# nico.net
KiCad netlist of a schematic drawn in EAGLE
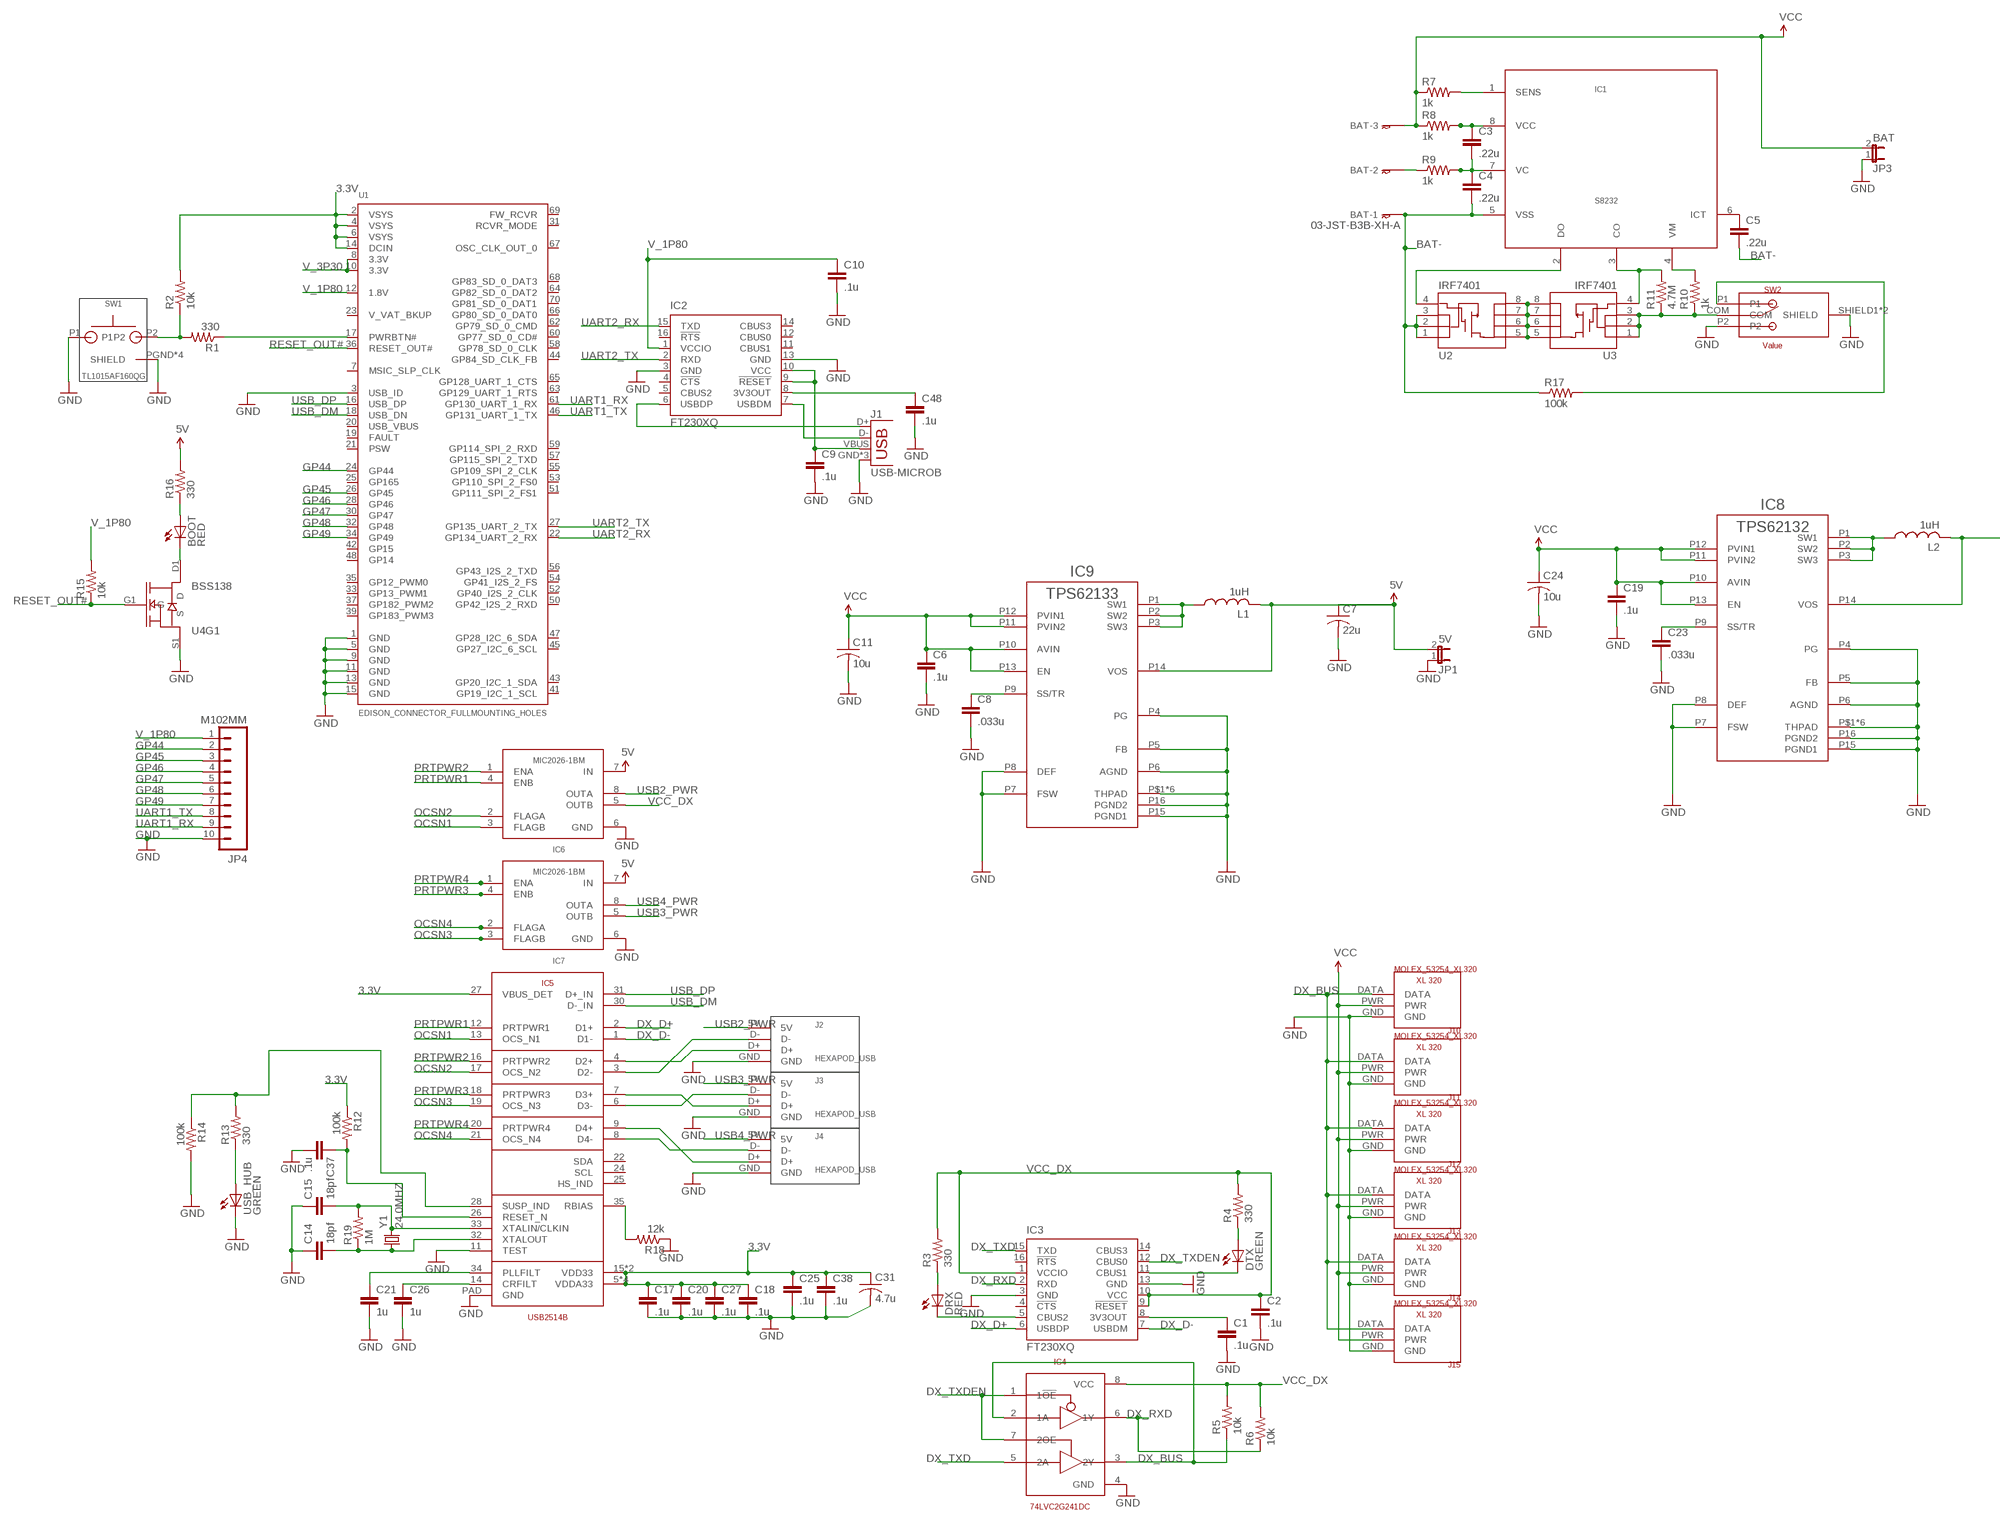
[diagram p0: schematic, sheet 1, part 1 of 2]
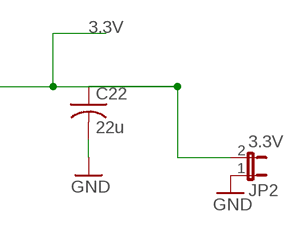
[diagram p1: schematic, sheet 1, part 2 of 2]

(export (version "E")
  (design (tool "Eeschema 10.0.6"))
  (components
    (comp (ref "BAT")
      (value "03-JST-B3B-XH-A")
      (footprint "eagle-import:B3B-XH")
      (libsource (lib "eagle-import") (part "03-JST-B3B-XH-A"))
    )
    (comp (ref "BOOT")
      (value "RED")
      (footprint "eagle-import:LED-0603")
      (libsource (lib "eagle-import") (part "LED0603"))
    )
    (comp (ref "C1")
      (value ".1u")
      (footprint "eagle-import:C0402")
      (libsource (lib "eagle-import") (part "C-EUC0402"))
    )
    (comp (ref "C2")
      (value ".1u")
      (footprint "eagle-import:C0402")
      (libsource (lib "eagle-import") (part "C-EUC0402"))
    )
    (comp (ref "C3")
      (value ".22u")
      (footprint "eagle-import:C0402")
      (libsource (lib "eagle-import") (part "C-EUC0402"))
    )
    (comp (ref "C4")
      (value ".22u")
      (footprint "eagle-import:C0402")
      (libsource (lib "eagle-import") (part "C-EUC0402"))
    )
    (comp (ref "C5")
      (value ".22u")
      (footprint "eagle-import:C0402")
      (libsource (lib "eagle-import") (part "C-EUC0402"))
    )
    (comp (ref "C6")
      (value ".1u")
      (footprint "eagle-import:C0402")
      (libsource (lib "eagle-import") (part "C-EUC0402"))
    )
    (comp (ref "C7")
      (value "22u")
      (footprint "eagle-import:C0603")
      (libsource (lib "eagle-import") (part "resistor_C-USC0603"))
    )
    (comp (ref "C8")
      (value ".033u")
      (footprint "eagle-import:C0402")
      (libsource (lib "eagle-import") (part "C-EUC0402"))
    )
    (comp (ref "C9")
      (value ".1u")
      (footprint "eagle-import:C0402")
      (libsource (lib "eagle-import") (part "C-EUC0402"))
    )
    (comp (ref "C10")
      (value ".1u")
      (footprint "eagle-import:C0402")
      (libsource (lib "eagle-import") (part "C-EUC0402"))
    )
    (comp (ref "C11")
      (value "10u")
      (footprint "eagle-import:C0805")
      (libsource (lib "eagle-import") (part "C-USC0805"))
    )
    (comp (ref "C14")
      (value "18pf")
      (footprint "eagle-import:C0402")
      (libsource (lib "eagle-import") (part "C-EUC0402"))
    )
    (comp (ref "C15")
      (value "18pf")
      (footprint "eagle-import:C0402")
      (libsource (lib "eagle-import") (part "C-EUC0402"))
    )
    (comp (ref "C17")
      (value ".1u")
      (footprint "eagle-import:C0402")
      (libsource (lib "eagle-import") (part "C-EUC0402"))
    )
    (comp (ref "C18")
      (value ".1u")
      (footprint "eagle-import:C0402")
      (libsource (lib "eagle-import") (part "C-EUC0402"))
    )
    (comp (ref "C19")
      (value ".1u")
      (footprint "eagle-import:C0402")
      (libsource (lib "eagle-import") (part "C-EUC0402"))
    )
    (comp (ref "C20")
      (value ".1u")
      (footprint "eagle-import:C0402")
      (libsource (lib "eagle-import") (part "C-EUC0402"))
    )
    (comp (ref "C21")
      (value "1u")
      (footprint "eagle-import:C0402")
      (libsource (lib "eagle-import") (part "C-EUC0402"))
    )
    (comp (ref "C22")
      (value "22u")
      (footprint "eagle-import:C0603")
      (libsource (lib "eagle-import") (part "resistor_C-USC0603"))
    )
    (comp (ref "C23")
      (value ".033u")
      (footprint "eagle-import:C0402")
      (libsource (lib "eagle-import") (part "C-EUC0402"))
    )
    (comp (ref "C24")
      (value "10u")
      (footprint "eagle-import:C0805")
      (libsource (lib "eagle-import") (part "C-USC0805"))
    )
    (comp (ref "C25")
      (value ".1u")
      (footprint "eagle-import:C0402")
      (libsource (lib "eagle-import") (part "C-EUC0402"))
    )
    (comp (ref "C26")
      (value "1u")
      (footprint "eagle-import:C0402")
      (libsource (lib "eagle-import") (part "C-EUC0402"))
    )
    (comp (ref "C27")
      (value ".1u")
      (footprint "eagle-import:C0402")
      (libsource (lib "eagle-import") (part "C-EUC0402"))
    )
    (comp (ref "C31")
      (value "4.7u")
      (footprint "eagle-import:C0603")
      (libsource (lib "eagle-import") (part "resistor_C-USC0603"))
    )
    (comp (ref "C37")
      (value ".1u")
      (footprint "eagle-import:C0402")
      (libsource (lib "eagle-import") (part "C-EUC0402"))
    )
    (comp (ref "C38")
      (value ".1u")
      (footprint "eagle-import:C0402")
      (libsource (lib "eagle-import") (part "C-EUC0402"))
    )
    (comp (ref "C48")
      (value ".1u")
      (footprint "eagle-import:C0402")
      (libsource (lib "eagle-import") (part "C-EUC0402"))
    )
    (comp (ref "DRX")
      (value "RED")
      (footprint "eagle-import:LED-0603")
      (libsource (lib "eagle-import") (part "LED0603"))
    )
    (comp (ref "DTX")
      (value "GREEN")
      (footprint "eagle-import:LED-0603")
      (libsource (lib "eagle-import") (part "LED0603"))
    )
    (comp (ref "IC1")
      (value "S8232")
      (footprint "eagle-import:TSSOP8")
      (libsource (lib "eagle-import") (part "S8232"))
    )
    (comp (ref "IC2")
      (value "FT230XQ")
      (footprint "eagle-import:QFN16")
      (libsource (lib "eagle-import") (part "FT230XQ"))
    )
    (comp (ref "IC3")
      (value "FT230XQ")
      (footprint "eagle-import:QFN16")
      (libsource (lib "eagle-import") (part "FT230XQ"))
    )
    (comp (ref "IC4")
      (value "74LVC2G241DC")
      (footprint "eagle-import:VSSOP")
      (libsource (lib "eagle-import") (part "74LVC2G241DC"))
    )
    (comp (ref "IC5")
      (value "USB2514B")
      (footprint "eagle-import:36-QFN")
      (libsource (lib "eagle-import") (part "USB2514B"))
    )
    (comp (ref "IC6")
      (value "MIC2026-1BM")
      (footprint "eagle-import:8-SOIC")
      (libsource (lib "eagle-import") (part "MIC2026-1BM"))
    )
    (comp (ref "IC7")
      (value "MIC2026-1BM")
      (footprint "eagle-import:8-SOIC")
      (libsource (lib "eagle-import") (part "MIC2026-1BM"))
    )
    (comp (ref "IC8")
      (value "TPS62132")
      (footprint "eagle-import:VQFN-16")
      (libsource (lib "eagle-import") (part "TPS62133"))
    )
    (comp (ref "IC9")
      (value "TPS62133")
      (footprint "eagle-import:VQFN-16")
      (libsource (lib "eagle-import") (part "TPS62133"))
    )
    (comp (ref "J1")
      (value "USB-MICROB")
      (footprint "eagle-import:USB-MICROB")
      (libsource (lib "eagle-import") (part "USB-MICROB"))
    )
    (comp (ref "J2")
      (value "HEXAPOD_USB")
      (footprint "eagle-import:MOLEX_53254_4POS")
      (libsource (lib "eagle-import") (part "HEXAPOD_USB"))
    )
    (comp (ref "J3")
      (value "HEXAPOD_USB")
      (footprint "eagle-import:MOLEX_53254_4POS")
      (libsource (lib "eagle-import") (part "HEXAPOD_USB"))
    )
    (comp (ref "J4")
      (value "HEXAPOD_USB")
      (footprint "eagle-import:MOLEX_53254_4POS")
      (libsource (lib "eagle-import") (part "HEXAPOD_USB"))
    )
    (comp (ref "J10")
      (value "MOLEX_53254_XL320")
      (footprint "eagle-import:MOLES_53254_XL320")
      (libsource (lib "eagle-import") (part "MOLEX_53254_XL320"))
    )
    (comp (ref "J11")
      (value "MOLEX_53254_XL320")
      (footprint "eagle-import:MOLES_53254_XL320")
      (libsource (lib "eagle-import") (part "MOLEX_53254_XL320"))
    )
    (comp (ref "J12")
      (value "MOLEX_53254_XL320")
      (footprint "eagle-import:MOLES_53254_XL320")
      (libsource (lib "eagle-import") (part "MOLEX_53254_XL320"))
    )
    (comp (ref "J13")
      (value "MOLEX_53254_XL320")
      (footprint "eagle-import:MOLES_53254_XL320")
      (libsource (lib "eagle-import") (part "MOLEX_53254_XL320"))
    )
    (comp (ref "J14")
      (value "MOLEX_53254_XL320")
      (footprint "eagle-import:MOLES_53254_XL320")
      (libsource (lib "eagle-import") (part "MOLEX_53254_XL320"))
    )
    (comp (ref "J15")
      (value "MOLEX_53254_XL320")
      (footprint "eagle-import:MOLES_53254_XL320")
      (libsource (lib "eagle-import") (part "MOLEX_53254_XL320"))
    )
    (comp (ref "JP1")
      (value "5V")
      (footprint "eagle-import:1X02")
      (libsource (lib "eagle-import") (part "JUMPER-2PTH"))
    )
    (comp (ref "JP2")
      (value "3.3V")
      (footprint "eagle-import:1X02")
      (libsource (lib "eagle-import") (part "JUMPER-2PTH"))
    )
    (comp (ref "JP3")
      (value "BAT")
      (footprint "eagle-import:1X02")
      (libsource (lib "eagle-import") (part "JUMPER-2PTH"))
    )
    (comp (ref "JP4")
      (value "M102MM")
      (footprint "eagle-import:1X10-2MM")
      (libsource (lib "eagle-import") (part "M102MM"))
    )
    (comp (ref "L1")
      (value "1uH")
      (footprint "eagle-import:L2825P")
      (libsource (lib "eagle-import") (part "L-USL2825P"))
    )
    (comp (ref "L2")
      (value "1uH")
      (footprint "eagle-import:L2825P")
      (libsource (lib "eagle-import") (part "L-USL2825P"))
    )
    (comp (ref "R1")
      (value "330")
      (footprint "eagle-import:R0402")
      (libsource (lib "eagle-import") (part "R-US_R0402"))
    )
    (comp (ref "R2")
      (value "10k")
      (footprint "eagle-import:R0402")
      (libsource (lib "eagle-import") (part "R-US_R0402"))
    )
    (comp (ref "R3")
      (value "330")
      (footprint "eagle-import:R0402")
      (libsource (lib "eagle-import") (part "R-US_R0402"))
    )
    (comp (ref "R4")
      (value "330")
      (footprint "eagle-import:R0402")
      (libsource (lib "eagle-import") (part "R-US_R0402"))
    )
    (comp (ref "R5")
      (value "10k")
      (footprint "eagle-import:R0402")
      (libsource (lib "eagle-import") (part "R-US_R0402"))
    )
    (comp (ref "R6")
      (value "10k")
      (footprint "eagle-import:R0402")
      (libsource (lib "eagle-import") (part "R-US_R0402"))
    )
    (comp (ref "R7")
      (value "1k")
      (footprint "eagle-import:C0402")
      (libsource (lib "eagle-import") (part "RESISTOR0402"))
    )
    (comp (ref "R8")
      (value "1k")
      (footprint "eagle-import:C0402")
      (libsource (lib "eagle-import") (part "RESISTOR0402"))
    )
    (comp (ref "R9")
      (value "1k")
      (footprint "eagle-import:C0402")
      (libsource (lib "eagle-import") (part "RESISTOR0402"))
    )
    (comp (ref "R10")
      (value "1k")
      (footprint "eagle-import:C0402")
      (libsource (lib "eagle-import") (part "RESISTOR0402"))
    )
    (comp (ref "R11")
      (value "4.7M")
      (footprint "eagle-import:C0402")
      (libsource (lib "eagle-import") (part "RESISTOR0402"))
    )
    (comp (ref "R12")
      (value "100k")
      (footprint "eagle-import:C0402")
      (libsource (lib "eagle-import") (part "RESISTOR0402"))
    )
    (comp (ref "R13")
      (value "330")
      (footprint "eagle-import:R0402")
      (libsource (lib "eagle-import") (part "R-US_R0402"))
    )
    (comp (ref "R14")
      (value "100k")
      (footprint "eagle-import:C0402")
      (libsource (lib "eagle-import") (part "RESISTOR0402"))
    )
    (comp (ref "R15")
      (value "10k")
      (footprint "eagle-import:R0402")
      (libsource (lib "eagle-import") (part "R-US_R0402"))
    )
    (comp (ref "R16")
      (value "330")
      (footprint "eagle-import:R0402")
      (libsource (lib "eagle-import") (part "R-US_R0402"))
    )
    (comp (ref "R17")
      (value "100k")
      (footprint "eagle-import:C0402")
      (libsource (lib "eagle-import") (part "RESISTOR0402"))
    )
    (comp (ref "R18")
      (value "12k")
      (footprint "eagle-import:C0402")
      (libsource (lib "eagle-import") (part "RESISTOR0402"))
    )
    (comp (ref "R19")
      (value "1M")
      (footprint "eagle-import:C0402")
      (libsource (lib "eagle-import") (part "RESISTOR0402"))
    )
    (comp (ref "SW1")
      (value "TL1015AF160QG")
      (footprint "eagle-import:TL1015AF160QG")
      (libsource (lib "eagle-import") (part "TL1015AF160QG"))
    )
    (comp (ref "SW2")
      (value "TOGGLE_SWITCH_ET01MD1AGE")
      (footprint "eagle-import:TOGGLE_SWITCH_ET01MD1AGE")
      (libsource (lib "eagle-import") (part "TOGGLE_SWITCH_ET01MD1AGE"))
    )
    (comp (ref "U1")
      (value "EDISON_CONNECTOR_FULLMOUNTING_HOLES")
      (footprint "eagle-import:EDISON_DAUGHTER")
      (libsource (lib "eagle-import") (part "EDISON_CONNECTOR_FULLMOUNTING_HOLES"))
    )
    (comp (ref "U2")
      (value "IRF7401")
      (footprint "eagle-import:SO08")
      (libsource (lib "eagle-import") (part "MOSFET-NCHANNEL-SOIC8"))
    )
    (comp (ref "U3")
      (value "IRF7401")
      (footprint "eagle-import:SO08")
      (libsource (lib "eagle-import") (part "MOSFET-NCHANNEL-SOIC8"))
    )
    (comp (ref "U4")
      (value "BSS138")
      (footprint "eagle-import:SOT363")
      (libsource (lib "eagle-import") (part "BSS138"))
    )
    (comp (ref "USB_HUB")
      (value "GREEN")
      (footprint "eagle-import:LED-0603")
      (libsource (lib "eagle-import") (part "LED0603"))
    )
    (comp (ref "Y1")
      (value "24.0MHZ")
      (footprint "eagle-import:CRYSTAL-SMD-5X3")
      (libsource (lib "eagle-import") (part "CRYSTAL5X3"))
    )
  )
  (nets
    (net (code "1") (name "/3.3V") (class "Default")
      (node (ref "C17") (pin "1") (pinfunction "1_1") (pintype "passive"))
      (node (ref "C18") (pin "1") (pinfunction "1_1") (pintype "passive"))
      (node (ref "C20") (pin "1") (pinfunction "1_1") (pintype "passive"))
      (node (ref "C22") (pin "1") (pinfunction "1_1") (pintype "passive"))
      (node (ref "C25") (pin "1") (pinfunction "1_1") (pintype "passive"))
      (node (ref "C27") (pin "1") (pinfunction "1_1") (pintype "passive"))
      (node (ref "C31") (pin "1") (pinfunction "1_1") (pintype "passive"))
      (node (ref "C38") (pin "1") (pinfunction "1_1") (pintype "passive"))
      (node (ref "IC5") (pin "10") (pinfunction "VDDA33_10") (pintype "bidirectional"))
      (node (ref "IC5") (pin "15") (pinfunction "VDD33_15") (pintype "bidirectional"))
      (node (ref "IC5") (pin "23") (pinfunction "VDD33_23") (pintype "bidirectional"))
      (node (ref "IC5") (pin "27") (pinfunction "VBUS_DET_27") (pintype "bidirectional"))
      (node (ref "IC5") (pin "29") (pinfunction "VDDA33_29") (pintype "bidirectional"))
      (node (ref "IC5") (pin "36") (pinfunction "VDDA33_36") (pintype "bidirectional"))
      (node (ref "IC5") (pin "5") (pinfunction "VDDA33_5") (pintype "bidirectional"))
      (node (ref "IC8") (pin "P14") (pinfunction "VOS_P14") (pintype "bidirectional"))
      (node (ref "JP2") (pin "2") (pinfunction "2_2") (pintype "passive"))
      (node (ref "L2") (pin "2") (pinfunction "2_2") (pintype "passive"))
      (node (ref "R12") (pin "1") (pinfunction "1_1") (pintype "passive"))
      (node (ref "R2") (pin "2") (pinfunction "2_2") (pintype "passive"))
      (node (ref "U1") (pin "14") (pinfunction "DCIN_14") (pintype "bidirectional"))
      (node (ref "U1") (pin "2") (pinfunction "VSYS_2") (pintype "bidirectional"))
      (node (ref "U1") (pin "4") (pinfunction "VSYS_4") (pintype "bidirectional"))
      (node (ref "U1") (pin "6") (pinfunction "VSYS_6") (pintype "bidirectional"))
    )
    (net (code "2") (name "/BAT-") (class "Default")
      (node (ref "BAT") (pin "P$1") (pinfunction "1_P$1") (pintype "passive"))
      (node (ref "C4") (pin "2") (pinfunction "2_2") (pintype "passive"))
      (node (ref "C5") (pin "2") (pinfunction "2_2") (pintype "passive"))
      (node (ref "IC1") (pin "5") (pinfunction "VSS_5") (pintype "bidirectional"))
      (node (ref "R17") (pin "1") (pinfunction "1_1") (pintype "passive"))
      (node (ref "U2") (pin "1") (pinfunction "S_1") (pintype "bidirectional"))
      (node (ref "U2") (pin "2") (pinfunction "S_2") (pintype "bidirectional"))
      (node (ref "U2") (pin "3") (pinfunction "S_3") (pintype "bidirectional"))
    )
    (net (code "3") (name "/DX_BUS") (class "Default")
      (node (ref "IC4") (pin "2") (pinfunction "1A_2") (pintype "bidirectional"))
      (node (ref "IC4") (pin "3") (pinfunction "2Y_3") (pintype "bidirectional"))
      (node (ref "J10") (pin "DATA") (pinfunction "DATA_DATA") (pintype "bidirectional"))
      (node (ref "J11") (pin "DATA") (pinfunction "DATA_DATA") (pintype "bidirectional"))
      (node (ref "J12") (pin "DATA") (pinfunction "DATA_DATA") (pintype "bidirectional"))
      (node (ref "J13") (pin "DATA") (pinfunction "DATA_DATA") (pintype "bidirectional"))
      (node (ref "J14") (pin "DATA") (pinfunction "DATA_DATA") (pintype "bidirectional"))
      (node (ref "J15") (pin "DATA") (pinfunction "DATA_DATA") (pintype "bidirectional"))
      (node (ref "R5") (pin "1") (pinfunction "1_1") (pintype "passive"))
    )
    (net (code "4") (name "/DX_D+") (class "Default")
      (node (ref "IC3") (pin "6") (pinfunction "USBDP_6") (pintype "input"))
      (node (ref "IC5") (pin "2") (pinfunction "D1+_2") (pintype "bidirectional"))
    )
    (net (code "5") (name "/DX_D-") (class "Default")
      (node (ref "IC3") (pin "7") (pinfunction "USBDM_7") (pintype "input"))
      (node (ref "IC5") (pin "1") (pinfunction "D1-_1") (pintype "bidirectional"))
    )
    (net (code "6") (name "/DX_RXD") (class "Default")
      (node (ref "IC3") (pin "2") (pinfunction "RXD_2") (pintype "input"))
      (node (ref "IC4") (pin "6") (pinfunction "1Y_6") (pintype "bidirectional"))
      (node (ref "R6") (pin "1") (pinfunction "1_1") (pintype "passive"))
    )
    (net (code "7") (name "/DX_TXD") (class "Default")
      (node (ref "IC3") (pin "15") (pinfunction "TXD_15") (pintype "output"))
      (node (ref "IC4") (pin "5") (pinfunction "2A_5") (pintype "bidirectional"))
    )
    (net (code "8") (name "/DX_TXDEN") (class "Default")
      (node (ref "IC3") (pin "12") (pinfunction "CBUS0_12") (pintype "bidirectional"))
      (node (ref "IC4") (pin "1") (pinfunction "1~{OE}_1") (pintype "bidirectional"))
      (node (ref "IC4") (pin "7") (pinfunction "2OE_7") (pintype "bidirectional"))
    )
    (net (code "9") (name "/GP44") (class "Default")
      (node (ref "JP4") (pin "2") (pinfunction "2_2") (pintype "passive"))
      (node (ref "U1") (pin "24") (pinfunction "GP44_24") (pintype "bidirectional"))
    )
    (net (code "10") (name "/GP45") (class "Default")
      (node (ref "JP4") (pin "3") (pinfunction "3_3") (pintype "passive"))
      (node (ref "U1") (pin "26") (pinfunction "GP45_26") (pintype "bidirectional"))
    )
    (net (code "11") (name "/GP46") (class "Default")
      (node (ref "JP4") (pin "4") (pinfunction "4_4") (pintype "passive"))
      (node (ref "U1") (pin "28") (pinfunction "GP46_28") (pintype "bidirectional"))
    )
    (net (code "12") (name "/GP47") (class "Default")
      (node (ref "JP4") (pin "5") (pinfunction "5_5") (pintype "passive"))
      (node (ref "U1") (pin "30") (pinfunction "GP47_30") (pintype "bidirectional"))
    )
    (net (code "13") (name "/GP48") (class "Default")
      (node (ref "JP4") (pin "6") (pinfunction "6_6") (pintype "passive"))
      (node (ref "U1") (pin "32") (pinfunction "GP48_32") (pintype "bidirectional"))
    )
    (net (code "14") (name "/GP49") (class "Default")
      (node (ref "JP4") (pin "7") (pinfunction "7_7") (pintype "passive"))
      (node (ref "U1") (pin "34") (pinfunction "GP49_34") (pintype "bidirectional"))
    )
    (net (code "15") (name "/OCSN1") (class "Default")
      (node (ref "IC5") (pin "13") (pinfunction "OCS_N1_13") (pintype "bidirectional"))
      (node (ref "IC6") (pin "3") (pinfunction "FLAGB_3") (pintype "bidirectional"))
    )
    (net (code "16") (name "/OCSN2") (class "Default")
      (node (ref "IC5") (pin "17") (pinfunction "OCS_N2_17") (pintype "bidirectional"))
      (node (ref "IC6") (pin "2") (pinfunction "FLAGA_2") (pintype "bidirectional"))
    )
    (net (code "17") (name "/OCSN3") (class "Default")
      (node (ref "IC5") (pin "19") (pinfunction "OCS_N3_19") (pintype "bidirectional"))
      (node (ref "IC7") (pin "3") (pinfunction "FLAGB_3") (pintype "bidirectional"))
    )
    (net (code "18") (name "/OCSN4") (class "Default")
      (node (ref "IC5") (pin "21") (pinfunction "OCS_N4_21") (pintype "bidirectional"))
      (node (ref "IC7") (pin "2") (pinfunction "FLAGA_2") (pintype "bidirectional"))
    )
    (net (code "19") (name "/PRTPWR1") (class "Default")
      (node (ref "IC5") (pin "12") (pinfunction "PRTPWR1_12") (pintype "bidirectional"))
      (node (ref "IC6") (pin "4") (pinfunction "ENB_4") (pintype "bidirectional"))
    )
    (net (code "20") (name "/PRTPWR2") (class "Default")
      (node (ref "IC5") (pin "16") (pinfunction "PRTPWR2_16") (pintype "bidirectional"))
      (node (ref "IC6") (pin "1") (pinfunction "ENA_1") (pintype "bidirectional"))
    )
    (net (code "21") (name "/PRTPWR3") (class "Default")
      (node (ref "IC5") (pin "18") (pinfunction "PRTPWR3_18") (pintype "bidirectional"))
      (node (ref "IC7") (pin "4") (pinfunction "ENB_4") (pintype "bidirectional"))
    )
    (net (code "22") (name "/PRTPWR4") (class "Default")
      (node (ref "IC5") (pin "20") (pinfunction "PRTPWR4_20") (pintype "bidirectional"))
      (node (ref "IC7") (pin "1") (pinfunction "ENA_1") (pintype "bidirectional"))
    )
    (net (code "23") (name "/RESET_OUT#") (class "Default")
      (node (ref "R15") (pin "1") (pinfunction "1_1") (pintype "passive"))
      (node (ref "U1") (pin "36") (pinfunction "RESET_OUT#_36") (pintype "bidirectional"))
      (node (ref "U4") (pin "G1") (pinfunction "G_G1") (pintype "bidirectional"))
    )
    (net (code "24") (name "/UART1_RX") (class "Default")
      (node (ref "JP4") (pin "9") (pinfunction "9_9") (pintype "passive"))
      (node (ref "U1") (pin "61") (pinfunction "GP130_UART_1_RX_61") (pintype "bidirectional"))
    )
    (net (code "25") (name "/UART1_TX") (class "Default")
      (node (ref "JP4") (pin "8") (pinfunction "8_8") (pintype "passive"))
      (node (ref "U1") (pin "46") (pinfunction "GP131_UART_1_TX_46") (pintype "bidirectional"))
    )
    (net (code "26") (name "/UART2_RX") (class "Default")
      (node (ref "IC2") (pin "15") (pinfunction "TXD_15") (pintype "output"))
      (node (ref "U1") (pin "22") (pinfunction "GP134_UART_2_RX_22") (pintype "bidirectional"))
    )
    (net (code "27") (name "/UART2_TX") (class "Default")
      (node (ref "IC2") (pin "2") (pinfunction "RXD_2") (pintype "input"))
      (node (ref "U1") (pin "27") (pinfunction "GP135_UART_2_TX_27") (pintype "bidirectional"))
    )
    (net (code "28") (name "/USB2_PWR") (class "Default")
      (node (ref "IC6") (pin "8") (pinfunction "OUTA_8") (pintype "bidirectional"))
      (node (ref "J2") (pin "5V") (pinfunction "5V_5V") (pintype "bidirectional"))
    )
    (net (code "29") (name "/USB3_PWR") (class "Default")
      (node (ref "IC7") (pin "5") (pinfunction "OUTB_5") (pintype "bidirectional"))
      (node (ref "J3") (pin "5V") (pinfunction "5V_5V") (pintype "bidirectional"))
    )
    (net (code "30") (name "/USB4_PWR") (class "Default")
      (node (ref "IC7") (pin "8") (pinfunction "OUTA_8") (pintype "bidirectional"))
      (node (ref "J4") (pin "5V") (pinfunction "5V_5V") (pintype "bidirectional"))
    )
    (net (code "31") (name "/USB_DM") (class "Default")
      (node (ref "IC5") (pin "30") (pinfunction "D-_IN_30") (pintype "bidirectional"))
      (node (ref "U1") (pin "18") (pinfunction "USB_DN_18") (pintype "bidirectional"))
    )
    (net (code "32") (name "/USB_DP") (class "Default")
      (node (ref "IC5") (pin "31") (pinfunction "D+_IN_31") (pintype "bidirectional"))
      (node (ref "U1") (pin "16") (pinfunction "USB_DP_16") (pintype "bidirectional"))
    )
    (net (code "33") (name "/VCC_DX") (class "Default")
      (node (ref "C2") (pin "1") (pinfunction "1_1") (pintype "passive"))
      (node (ref "IC3") (pin "1") (pinfunction "VCCIO_1") (pintype "power_in"))
      (node (ref "IC3") (pin "10") (pinfunction "VCC_10") (pintype "power_in"))
      (node (ref "IC3") (pin "9") (pinfunction "~{RESET}_9") (pintype "input"))
      (node (ref "IC4") (pin "8") (pinfunction "VCC_8") (pintype "bidirectional"))
      (node (ref "IC6") (pin "5") (pinfunction "OUTB_5") (pintype "bidirectional"))
      (node (ref "R3") (pin "2") (pinfunction "2_2") (pintype "passive"))
      (node (ref "R4") (pin "2") (pinfunction "2_2") (pintype "passive"))
      (node (ref "R5") (pin "2") (pinfunction "2_2") (pintype "passive"))
      (node (ref "R6") (pin "2") (pinfunction "2_2") (pintype "passive"))
    )
    (net (code "34") (name "/V_1P80") (class "Default")
      (node (ref "C10") (pin "1") (pinfunction "1_1") (pintype "passive"))
      (node (ref "IC2") (pin "1") (pinfunction "VCCIO_1") (pintype "power_in"))
      (node (ref "JP4") (pin "1") (pinfunction "1_1") (pintype "passive"))
      (node (ref "R15") (pin "2") (pinfunction "2_2") (pintype "passive"))
      (node (ref "U1") (pin "12") (pinfunction "1.8V_12") (pintype "bidirectional"))
    )
    (net (code "35") (name "/V_3P30") (class "Default")
      (node (ref "U1") (pin "10") (pinfunction "3.3V_10") (pintype "bidirectional"))
      (node (ref "U1") (pin "8") (pinfunction "3.3V_8") (pintype "bidirectional"))
    )
    (net (code "36") (name "5V") (class "Default")
      (node (ref "C7") (pin "1") (pinfunction "1_1") (pintype "passive"))
      (node (ref "IC6") (pin "7") (pinfunction "IN_7") (pintype "bidirectional"))
      (node (ref "IC7") (pin "7") (pinfunction "IN_7") (pintype "bidirectional"))
      (node (ref "IC9") (pin "P14") (pinfunction "VOS_P14") (pintype "bidirectional"))
      (node (ref "JP1") (pin "2") (pinfunction "2_2") (pintype "passive"))
      (node (ref "L1") (pin "2") (pinfunction "2_2") (pintype "passive"))
      (node (ref "R16") (pin "2") (pinfunction "2_2") (pintype "passive"))
    )
    (net (code "37") (name "GND") (class "Default")
      (node (ref "C1") (pin "2") (pinfunction "2_2") (pintype "passive"))
      (node (ref "C10") (pin "2") (pinfunction "2_2") (pintype "passive"))
      (node (ref "C11") (pin "2") (pinfunction "2_2") (pintype "passive"))
      (node (ref "C14") (pin "1") (pinfunction "1_1") (pintype "passive"))
      (node (ref "C15") (pin "1") (pinfunction "1_1") (pintype "passive"))
      (node (ref "C17") (pin "2") (pinfunction "2_2") (pintype "passive"))
      (node (ref "C18") (pin "2") (pinfunction "2_2") (pintype "passive"))
      (node (ref "C19") (pin "2") (pinfunction "2_2") (pintype "passive"))
      (node (ref "C2") (pin "2") (pinfunction "2_2") (pintype "passive"))
      (node (ref "C20") (pin "2") (pinfunction "2_2") (pintype "passive"))
      (node (ref "C21") (pin "2") (pinfunction "2_2") (pintype "passive"))
      (node (ref "C22") (pin "2") (pinfunction "2_2") (pintype "passive"))
      (node (ref "C23") (pin "2") (pinfunction "2_2") (pintype "passive"))
      (node (ref "C24") (pin "2") (pinfunction "2_2") (pintype "passive"))
      (node (ref "C25") (pin "2") (pinfunction "2_2") (pintype "passive"))
      (node (ref "C26") (pin "2") (pinfunction "2_2") (pintype "passive"))
      (node (ref "C27") (pin "2") (pinfunction "2_2") (pintype "passive"))
      (node (ref "C31") (pin "2") (pinfunction "2_2") (pintype "passive"))
      (node (ref "C37") (pin "2") (pinfunction "2_2") (pintype "passive"))
      (node (ref "C38") (pin "2") (pinfunction "2_2") (pintype "passive"))
      (node (ref "C48") (pin "2") (pinfunction "2_2") (pintype "passive"))
      (node (ref "C6") (pin "2") (pinfunction "2_2") (pintype "passive"))
      (node (ref "C7") (pin "2") (pinfunction "2_2") (pintype "passive"))
      (node (ref "C8") (pin "2") (pinfunction "2_2") (pintype "passive"))
      (node (ref "C9") (pin "2") (pinfunction "2_2") (pintype "passive"))
      (node (ref "IC2") (pin "13") (pinfunction "GND_13") (pintype "power_in"))
      (node (ref "IC2") (pin "3") (pinfunction "GND_3") (pintype "power_in"))
      (node (ref "IC3") (pin "13") (pinfunction "GND_13") (pintype "power_in"))
      (node (ref "IC3") (pin "3") (pinfunction "GND_3") (pintype "power_in"))
      (node (ref "IC4") (pin "4") (pinfunction "GND_4") (pintype "bidirectional"))
      (node (ref "IC5") (pin "11") (pinfunction "TEST_11") (pintype "bidirectional"))
      (node (ref "IC5") (pin "PAD") (pinfunction "GND_PAD") (pintype "bidirectional"))
      (node (ref "IC6") (pin "6") (pinfunction "GND_6") (pintype "bidirectional"))
      (node (ref "IC7") (pin "6") (pinfunction "GND_6") (pintype "bidirectional"))
      (node (ref "IC8") (pin "P$1") (pinfunction "THPAD_P$1") (pintype "bidirectional"))
      (node (ref "IC8") (pin "P$2") (pinfunction "THPAD_P$2") (pintype "bidirectional"))
      (node (ref "IC8") (pin "P$3") (pinfunction "THPAD_P$3") (pintype "bidirectional"))
      (node (ref "IC8") (pin "P$4") (pinfunction "THPAD_P$4") (pintype "bidirectional"))
      (node (ref "IC8") (pin "P$5") (pinfunction "THPAD_P$5") (pintype "bidirectional"))
      (node (ref "IC8") (pin "P$6") (pinfunction "THPAD_P$6") (pintype "bidirectional"))
      (node (ref "IC8") (pin "P15") (pinfunction "PGND1_P15") (pintype "bidirectional"))
      (node (ref "IC8") (pin "P16") (pinfunction "PGND2_P16") (pintype "bidirectional"))
      (node (ref "IC8") (pin "P4") (pinfunction "PG_P4") (pintype "bidirectional"))
      (node (ref "IC8") (pin "P5") (pinfunction "FB_P5") (pintype "bidirectional"))
      (node (ref "IC8") (pin "P6") (pinfunction "AGND_P6") (pintype "bidirectional"))
      (node (ref "IC8") (pin "P7") (pinfunction "FSW_P7") (pintype "bidirectional"))
      (node (ref "IC8") (pin "P8") (pinfunction "DEF_P8") (pintype "bidirectional"))
      (node (ref "IC9") (pin "P$1") (pinfunction "THPAD_P$1") (pintype "bidirectional"))
      (node (ref "IC9") (pin "P$2") (pinfunction "THPAD_P$2") (pintype "bidirectional"))
      (node (ref "IC9") (pin "P$3") (pinfunction "THPAD_P$3") (pintype "bidirectional"))
      (node (ref "IC9") (pin "P$4") (pinfunction "THPAD_P$4") (pintype "bidirectional"))
      (node (ref "IC9") (pin "P$5") (pinfunction "THPAD_P$5") (pintype "bidirectional"))
      (node (ref "IC9") (pin "P$6") (pinfunction "THPAD_P$6") (pintype "bidirectional"))
      (node (ref "IC9") (pin "P15") (pinfunction "PGND1_P15") (pintype "bidirectional"))
      (node (ref "IC9") (pin "P16") (pinfunction "PGND2_P16") (pintype "bidirectional"))
      (node (ref "IC9") (pin "P4") (pinfunction "PG_P4") (pintype "bidirectional"))
      (node (ref "IC9") (pin "P5") (pinfunction "FB_P5") (pintype "bidirectional"))
      (node (ref "IC9") (pin "P6") (pinfunction "AGND_P6") (pintype "bidirectional"))
      (node (ref "IC9") (pin "P7") (pinfunction "FSW_P7") (pintype "bidirectional"))
      (node (ref "IC9") (pin "P8") (pinfunction "DEF_P8") (pintype "bidirectional"))
      (node (ref "J1") (pin "GND") (pinfunction "GND_GND") (pintype "bidirectional"))
      (node (ref "J1") (pin "MT1") (pinfunction "GND_MT1") (pintype "bidirectional"))
      (node (ref "J1") (pin "MT2") (pinfunction "GND_MT2") (pintype "bidirectional"))
      (node (ref "J10") (pin "GND") (pinfunction "GND_GND") (pintype "bidirectional"))
      (node (ref "J11") (pin "GND") (pinfunction "GND_GND") (pintype "bidirectional"))
      (node (ref "J12") (pin "GND") (pinfunction "GND_GND") (pintype "bidirectional"))
      (node (ref "J13") (pin "GND") (pinfunction "GND_GND") (pintype "bidirectional"))
      (node (ref "J14") (pin "GND") (pinfunction "GND_GND") (pintype "bidirectional"))
      (node (ref "J15") (pin "GND") (pinfunction "GND_GND") (pintype "bidirectional"))
      (node (ref "J2") (pin "GND") (pinfunction "GND_GND") (pintype "bidirectional"))
      (node (ref "J3") (pin "GND") (pinfunction "GND_GND") (pintype "bidirectional"))
      (node (ref "J4") (pin "GND") (pinfunction "GND_GND") (pintype "bidirectional"))
      (node (ref "JP1") (pin "1") (pinfunction "1_1") (pintype "passive"))
      (node (ref "JP2") (pin "1") (pinfunction "1_1") (pintype "passive"))
      (node (ref "JP3") (pin "1") (pinfunction "1_1") (pintype "passive"))
      (node (ref "JP4") (pin "10") (pinfunction "10_10") (pintype "passive"))
      (node (ref "R14") (pin "2") (pinfunction "2_2") (pintype "passive"))
      (node (ref "R18") (pin "1") (pinfunction "1_1") (pintype "passive"))
      (node (ref "SW1") (pin "P1") (pinfunction "P1_P1") (pintype "bidirectional"))
      (node (ref "SW1") (pin "PGND") (pinfunction "SHIELD_PGND") (pintype "bidirectional"))
      (node (ref "SW1") (pin "PGND2") (pinfunction "SHIELD_PGND2") (pintype "bidirectional"))
      (node (ref "SW1") (pin "PGND3") (pinfunction "SHIELD_PGND3") (pintype "bidirectional"))
      (node (ref "SW1") (pin "PGND4") (pinfunction "SHIELD_PGND4") (pintype "bidirectional"))
      (node (ref "SW2") (pin "P2") (pinfunction "P2_P2") (pintype "bidirectional"))
      (node (ref "SW2") (pin "SHIELD1") (pinfunction "SHIELD_SHIELD1") (pintype "bidirectional"))
      (node (ref "SW2") (pin "SHIELD2") (pinfunction "SHIELD_SHIELD2") (pintype "bidirectional"))
      (node (ref "U1") (pin "1") (pinfunction "GND_1") (pintype "bidirectional"))
      (node (ref "U1") (pin "11") (pinfunction "GND_11") (pintype "bidirectional"))
      (node (ref "U1") (pin "13") (pinfunction "GND_13") (pintype "bidirectional"))
      (node (ref "U1") (pin "15") (pinfunction "GND_15") (pintype "bidirectional"))
      (node (ref "U1") (pin "3") (pinfunction "USB_ID_3") (pintype "bidirectional"))
      (node (ref "U1") (pin "5") (pinfunction "GND_5") (pintype "bidirectional"))
      (node (ref "U1") (pin "9") (pinfunction "GND_9") (pintype "bidirectional"))
      (node (ref "U4") (pin "S1") (pinfunction "S_S1") (pintype "bidirectional"))
      (node (ref "USB_HUB") (pin "C") (pinfunction "C_C") (pintype "passive"))
    )
    (net (code "38") (name "Net-(BATB-1)") (class "Default")
      (node (ref "BAT") (pin "P$2") (pinfunction "1_P$2") (pintype "passive"))
      (node (ref "R9") (pin "1") (pinfunction "1_1") (pintype "passive"))
    )
    (net (code "39") (name "Net-(BOOT-PadA)") (class "Default")
      (node (ref "BOOT") (pin "A") (pinfunction "A_A") (pintype "passive"))
      (node (ref "R16") (pin "1") (pinfunction "1_1") (pintype "passive"))
    )
    (net (code "40") (name "Net-(DRX-PadA)") (class "Default")
      (node (ref "DRX") (pin "A") (pinfunction "A_A") (pintype "passive"))
      (node (ref "R3") (pin "1") (pinfunction "1_1") (pintype "passive"))
    )
    (net (code "41") (name "Net-(DTX-PadA)") (class "Default")
      (node (ref "DTX") (pin "A") (pinfunction "A_A") (pintype "passive"))
      (node (ref "R4") (pin "1") (pinfunction "1_1") (pintype "passive"))
    )
    (net (code "42") (name "Net-(IC1-CO)") (class "Default")
      (node (ref "IC1") (pin "3") (pinfunction "CO_3") (pintype "bidirectional"))
      (node (ref "R11") (pin "2") (pinfunction "2_2") (pintype "passive"))
      (node (ref "U3") (pin "4") (pinfunction "G_4") (pintype "bidirectional"))
    )
    (net (code "43") (name "Net-(IC1-DO)") (class "Default")
      (node (ref "IC1") (pin "2") (pinfunction "DO_2") (pintype "bidirectional"))
      (node (ref "U2") (pin "4") (pinfunction "G_4") (pintype "bidirectional"))
    )
    (net (code "44") (name "Net-(IC1-ICT)") (class "Default")
      (node (ref "C5") (pin "1") (pinfunction "1_1") (pintype "passive"))
      (node (ref "IC1") (pin "6") (pinfunction "ICT_6") (pintype "bidirectional"))
    )
    (net (code "45") (name "Net-(IC1-SENS)") (class "Default")
      (node (ref "IC1") (pin "1") (pinfunction "SENS_1") (pintype "bidirectional"))
      (node (ref "R7") (pin "2") (pinfunction "2_2") (pintype "passive"))
    )
    (net (code "46") (name "Net-(IC1-VC)") (class "Default")
      (node (ref "C3") (pin "2") (pinfunction "2_2") (pintype "passive"))
      (node (ref "C4") (pin "1") (pinfunction "1_1") (pintype "passive"))
      (node (ref "IC1") (pin "7") (pinfunction "VC_7") (pintype "bidirectional"))
      (node (ref "R9") (pin "2") (pinfunction "2_2") (pintype "passive"))
    )
    (net (code "47") (name "Net-(IC1-VCC)") (class "Default")
      (node (ref "C3") (pin "1") (pinfunction "1_1") (pintype "passive"))
      (node (ref "IC1") (pin "8") (pinfunction "VCC_8") (pintype "bidirectional"))
      (node (ref "R8") (pin "2") (pinfunction "2_2") (pintype "passive"))
    )
    (net (code "48") (name "Net-(IC1-VM)") (class "Default")
      (node (ref "IC1") (pin "4") (pinfunction "VM_4") (pintype "bidirectional"))
      (node (ref "R10") (pin "2") (pinfunction "2_2") (pintype "passive"))
    )
    (net (code "49") (name "Net-(IC2-3V3OUT)") (class "Default")
      (node (ref "C48") (pin "1") (pinfunction "1_1") (pintype "passive"))
      (node (ref "IC2") (pin "8") (pinfunction "3V3OUT_8") (pintype "output"))
    )
    (net (code "50") (name "Net-(IC2-USBDM)") (class "Default")
      (node (ref "IC2") (pin "7") (pinfunction "USBDM_7") (pintype "input"))
      (node (ref "J1") (pin "D-") (pinfunction "D-_D-") (pintype "bidirectional"))
    )
    (net (code "51") (name "Net-(IC2-USBDP)") (class "Default")
      (node (ref "IC2") (pin "6") (pinfunction "USBDP_6") (pintype "input"))
      (node (ref "J1") (pin "D+") (pinfunction "D+_D+") (pintype "bidirectional"))
    )
    (net (code "52") (name "Net-(IC2-VCC)") (class "Default")
      (node (ref "C9") (pin "1") (pinfunction "1_1") (pintype "passive"))
      (node (ref "IC2") (pin "10") (pinfunction "VCC_10") (pintype "power_in"))
      (node (ref "IC2") (pin "9") (pinfunction "~{RESET}_9") (pintype "input"))
      (node (ref "J1") (pin "VBUS") (pinfunction "VBUS_VBUS") (pintype "bidirectional"))
    )
    (net (code "53") (name "Net-(IC3-3V3OUT)") (class "Default")
      (node (ref "C1") (pin "1") (pinfunction "1_1") (pintype "passive"))
      (node (ref "IC3") (pin "8") (pinfunction "3V3OUT_8") (pintype "output"))
    )
    (net (code "54") (name "Net-(IC3-CBUS1)") (class "Default")
      (node (ref "DTX") (pin "C") (pinfunction "C_C") (pintype "passive"))
      (node (ref "IC3") (pin "11") (pinfunction "CBUS1_11") (pintype "bidirectional"))
    )
    (net (code "55") (name "Net-(IC3-CBUS2)") (class "Default")
      (node (ref "DRX") (pin "C") (pinfunction "C_C") (pintype "passive"))
      (node (ref "IC3") (pin "5") (pinfunction "CBUS2_5") (pintype "bidirectional"))
    )
    (net (code "56") (name "Net-(IC5-CRFILT)") (class "Default")
      (node (ref "C26") (pin "1") (pinfunction "1_1") (pintype "passive"))
      (node (ref "IC5") (pin "14") (pinfunction "CRFILT_14") (pintype "bidirectional"))
    )
    (net (code "57") (name "Net-(IC5-D2+)") (class "Default")
      (node (ref "IC5") (pin "4") (pinfunction "D2+_4") (pintype "bidirectional"))
      (node (ref "J2") (pin "D+") (pinfunction "D+_D+") (pintype "bidirectional"))
    )
    (net (code "58") (name "Net-(IC5-D2-)") (class "Default")
      (node (ref "IC5") (pin "3") (pinfunction "D2-_3") (pintype "bidirectional"))
      (node (ref "J2") (pin "D-") (pinfunction "D-_D-") (pintype "bidirectional"))
    )
    (net (code "59") (name "Net-(IC5-D3+)") (class "Default")
      (node (ref "IC5") (pin "7") (pinfunction "D3+_7") (pintype "bidirectional"))
      (node (ref "J3") (pin "D+") (pinfunction "D+_D+") (pintype "bidirectional"))
    )
    (net (code "60") (name "Net-(IC5-D3-)") (class "Default")
      (node (ref "IC5") (pin "6") (pinfunction "D3-_6") (pintype "bidirectional"))
      (node (ref "J3") (pin "D-") (pinfunction "D-_D-") (pintype "bidirectional"))
    )
    (net (code "61") (name "Net-(IC5-D4+)") (class "Default")
      (node (ref "IC5") (pin "9") (pinfunction "D4+_9") (pintype "bidirectional"))
      (node (ref "J4") (pin "D+") (pinfunction "D+_D+") (pintype "bidirectional"))
    )
    (net (code "62") (name "Net-(IC5-D4-)") (class "Default")
      (node (ref "IC5") (pin "8") (pinfunction "D4-_8") (pintype "bidirectional"))
      (node (ref "J4") (pin "D-") (pinfunction "D-_D-") (pintype "bidirectional"))
    )
    (net (code "63") (name "Net-(IC5-PLLFILT)") (class "Default")
      (node (ref "C21") (pin "1") (pinfunction "1_1") (pintype "passive"))
      (node (ref "IC5") (pin "34") (pinfunction "PLLFILT_34") (pintype "bidirectional"))
    )
    (net (code "64") (name "Net-(IC5-RBIAS)") (class "Default")
      (node (ref "IC5") (pin "35") (pinfunction "RBIAS_35") (pintype "bidirectional"))
      (node (ref "R18") (pin "2") (pinfunction "2_2") (pintype "passive"))
    )
    (net (code "65") (name "Net-(IC5-RESET_N)") (class "Default")
      (node (ref "C37") (pin "1") (pinfunction "1_1") (pintype "passive"))
      (node (ref "IC5") (pin "26") (pinfunction "RESET_N_26") (pintype "bidirectional"))
      (node (ref "R12") (pin "2") (pinfunction "2_2") (pintype "passive"))
    )
    (net (code "66") (name "Net-(IC5-SUSP_IND)") (class "Default")
      (node (ref "IC5") (pin "28") (pinfunction "SUSP_IND_28") (pintype "bidirectional"))
      (node (ref "R13") (pin "2") (pinfunction "2_2") (pintype "passive"))
      (node (ref "R14") (pin "1") (pinfunction "1_1") (pintype "passive"))
    )
    (net (code "67") (name "Net-(IC5-XTALIN{slash}CLKIN)") (class "Default")
      (node (ref "C15") (pin "2") (pinfunction "2_2") (pintype "passive"))
      (node (ref "IC5") (pin "33") (pinfunction "XTALIN/CLKIN_33") (pintype "bidirectional"))
      (node (ref "R19") (pin "2") (pinfunction "2_2") (pintype "passive"))
      (node (ref "Y1") (pin "3") (pinfunction "2_3") (pintype "passive"))
    )
    (net (code "68") (name "Net-(IC5-XTALOUT)") (class "Default")
      (node (ref "C14") (pin "2") (pinfunction "2_2") (pintype "passive"))
      (node (ref "IC5") (pin "32") (pinfunction "XTALOUT_32") (pintype "bidirectional"))
      (node (ref "R19") (pin "1") (pinfunction "1_1") (pintype "passive"))
      (node (ref "Y1") (pin "1") (pinfunction "1_1") (pintype "passive"))
    )
    (net (code "69") (name "Net-(IC8-SS{slash}TR)") (class "Default")
      (node (ref "C23") (pin "1") (pinfunction "1_1") (pintype "passive"))
      (node (ref "IC8") (pin "P9") (pinfunction "SS/TR_P9") (pintype "bidirectional"))
    )
    (net (code "70") (name "Net-(IC8-SW1)") (class "Default")
      (node (ref "IC8") (pin "P1") (pinfunction "SW1_P1") (pintype "bidirectional"))
      (node (ref "IC8") (pin "P2") (pinfunction "SW2_P2") (pintype "bidirectional"))
      (node (ref "IC8") (pin "P3") (pinfunction "SW3_P3") (pintype "bidirectional"))
      (node (ref "L2") (pin "1") (pinfunction "1_1") (pintype "passive"))
    )
    (net (code "71") (name "Net-(IC9-SS{slash}TR)") (class "Default")
      (node (ref "C8") (pin "1") (pinfunction "1_1") (pintype "passive"))
      (node (ref "IC9") (pin "P9") (pinfunction "SS/TR_P9") (pintype "bidirectional"))
    )
    (net (code "72") (name "Net-(IC9-SW1)") (class "Default")
      (node (ref "IC9") (pin "P1") (pinfunction "SW1_P1") (pintype "bidirectional"))
      (node (ref "IC9") (pin "P2") (pinfunction "SW2_P2") (pintype "bidirectional"))
      (node (ref "IC9") (pin "P3") (pinfunction "SW3_P3") (pintype "bidirectional"))
      (node (ref "L1") (pin "1") (pinfunction "1_1") (pintype "passive"))
    )
    (net (code "73") (name "Net-(R1-Pad2)") (class "Default")
      (node (ref "R1") (pin "2") (pinfunction "2_2") (pintype "passive"))
      (node (ref "R2") (pin "1") (pinfunction "1_1") (pintype "passive"))
      (node (ref "SW1") (pin "P2") (pinfunction "P2_P2") (pintype "bidirectional"))
    )
    (net (code "74") (name "Net-(R10-Pad1)") (class "Default")
      (node (ref "R10") (pin "1") (pinfunction "1_1") (pintype "passive"))
      (node (ref "R11") (pin "1") (pinfunction "1_1") (pintype "passive"))
      (node (ref "SW2") (pin "COM") (pinfunction "COM_COM") (pintype "bidirectional"))
      (node (ref "U3") (pin "1") (pinfunction "S_1") (pintype "bidirectional"))
      (node (ref "U3") (pin "2") (pinfunction "S_2") (pintype "bidirectional"))
      (node (ref "U3") (pin "3") (pinfunction "S_3") (pintype "bidirectional"))
    )
    (net (code "75") (name "Net-(R13-Pad1)") (class "Default")
      (node (ref "R13") (pin "1") (pinfunction "1_1") (pintype "passive"))
      (node (ref "USB_HUB") (pin "A") (pinfunction "A_A") (pintype "passive"))
    )
    (net (code "76") (name "Net-(R17-Pad2)") (class "Default")
      (node (ref "R17") (pin "2") (pinfunction "2_2") (pintype "passive"))
      (node (ref "SW2") (pin "P1") (pinfunction "P1_P1") (pintype "bidirectional"))
    )
    (net (code "77") (name "Net-(U1-PWRBTN#)") (class "Default")
      (node (ref "R1") (pin "1") (pinfunction "1_1") (pintype "passive"))
      (node (ref "U1") (pin "17") (pinfunction "PWRBTN#_17") (pintype "bidirectional"))
    )
    (net (code "78") (name "Net-(U2-D-Pad5)") (class "Default")
      (node (ref "U2") (pin "5") (pinfunction "D_5") (pintype "bidirectional"))
      (node (ref "U2") (pin "6") (pinfunction "D_6") (pintype "bidirectional"))
      (node (ref "U2") (pin "7") (pinfunction "D_7") (pintype "bidirectional"))
      (node (ref "U2") (pin "8") (pinfunction "D_8") (pintype "bidirectional"))
      (node (ref "U3") (pin "5") (pinfunction "D_5") (pintype "bidirectional"))
      (node (ref "U3") (pin "6") (pinfunction "D_6") (pintype "bidirectional"))
      (node (ref "U3") (pin "7") (pinfunction "D_7") (pintype "bidirectional"))
      (node (ref "U3") (pin "8") (pinfunction "D_8") (pintype "bidirectional"))
    )
    (net (code "79") (name "Net-(U4A-D)") (class "Default")
      (node (ref "BOOT") (pin "C") (pinfunction "C_C") (pintype "passive"))
      (node (ref "U4") (pin "D1") (pinfunction "D_D1") (pintype "bidirectional"))
    )
    (net (code "80") (name "VCC") (class "Default")
      (node (ref "BAT") (pin "P$3") (pinfunction "1_P$3") (pintype "passive"))
      (node (ref "C11") (pin "1") (pinfunction "1_1") (pintype "passive"))
      (node (ref "C19") (pin "1") (pinfunction "1_1") (pintype "passive"))
      (node (ref "C24") (pin "1") (pinfunction "1_1") (pintype "passive"))
      (node (ref "C6") (pin "1") (pinfunction "1_1") (pintype "passive"))
      (node (ref "IC8") (pin "P10") (pinfunction "AVIN_P10") (pintype "bidirectional"))
      (node (ref "IC8") (pin "P11") (pinfunction "PVIN2_P11") (pintype "bidirectional"))
      (node (ref "IC8") (pin "P12") (pinfunction "PVIN1_P12") (pintype "bidirectional"))
      (node (ref "IC8") (pin "P13") (pinfunction "EN_P13") (pintype "bidirectional"))
      (node (ref "IC9") (pin "P10") (pinfunction "AVIN_P10") (pintype "bidirectional"))
      (node (ref "IC9") (pin "P11") (pinfunction "PVIN2_P11") (pintype "bidirectional"))
      (node (ref "IC9") (pin "P12") (pinfunction "PVIN1_P12") (pintype "bidirectional"))
      (node (ref "IC9") (pin "P13") (pinfunction "EN_P13") (pintype "bidirectional"))
      (node (ref "J10") (pin "PWR") (pinfunction "PWR_PWR") (pintype "bidirectional"))
      (node (ref "J11") (pin "PWR") (pinfunction "PWR_PWR") (pintype "bidirectional"))
      (node (ref "J12") (pin "PWR") (pinfunction "PWR_PWR") (pintype "bidirectional"))
      (node (ref "J13") (pin "PWR") (pinfunction "PWR_PWR") (pintype "bidirectional"))
      (node (ref "J14") (pin "PWR") (pinfunction "PWR_PWR") (pintype "bidirectional"))
      (node (ref "J15") (pin "PWR") (pinfunction "PWR_PWR") (pintype "bidirectional"))
      (node (ref "JP3") (pin "2") (pinfunction "2_2") (pintype "passive"))
      (node (ref "R7") (pin "1") (pinfunction "1_1") (pintype "passive"))
      (node (ref "R8") (pin "1") (pinfunction "1_1") (pintype "passive"))
    )
    (net (code "81") (name "unconnected-(IC2-CBUS0-Pad12)") (class "Default")
      (node (ref "IC2") (pin "12") (pinfunction "CBUS0_12") (pintype "bidirectional"))
    )
    (net (code "82") (name "unconnected-(IC2-CBUS1-Pad11)") (class "Default")
      (node (ref "IC2") (pin "11") (pinfunction "CBUS1_11") (pintype "bidirectional"))
    )
    (net (code "83") (name "unconnected-(IC2-CBUS2-Pad5)") (class "Default")
      (node (ref "IC2") (pin "5") (pinfunction "CBUS2_5") (pintype "bidirectional"))
    )
    (net (code "84") (name "unconnected-(IC2-CBUS3-Pad14)") (class "Default")
      (node (ref "IC2") (pin "14") (pinfunction "CBUS3_14") (pintype "bidirectional"))
    )
    (net (code "85") (name "unconnected-(IC2-~{CTS}-Pad4)") (class "Default")
      (node (ref "IC2") (pin "4") (pinfunction "~{CTS}_4") (pintype "input"))
    )
    (net (code "86") (name "unconnected-(IC2-~{RTS}-Pad16)") (class "Default")
      (node (ref "IC2") (pin "16") (pinfunction "~{RTS}_16") (pintype "output"))
    )
    (net (code "87") (name "unconnected-(IC3-CBUS3-Pad14)") (class "Default")
      (node (ref "IC3") (pin "14") (pinfunction "CBUS3_14") (pintype "bidirectional"))
    )
    (net (code "88") (name "unconnected-(IC3-~{CTS}-Pad4)") (class "Default")
      (node (ref "IC3") (pin "4") (pinfunction "~{CTS}_4") (pintype "input"))
    )
    (net (code "89") (name "unconnected-(IC3-~{RTS}-Pad16)") (class "Default")
      (node (ref "IC3") (pin "16") (pinfunction "~{RTS}_16") (pintype "output"))
    )
    (net (code "90") (name "unconnected-(IC5-HS_IND-Pad25)") (class "Default")
      (node (ref "IC5") (pin "25") (pinfunction "HS_IND_25") (pintype "bidirectional"))
    )
    (net (code "91") (name "unconnected-(IC5-SCL-Pad24)") (class "Default")
      (node (ref "IC5") (pin "24") (pinfunction "SCL_24") (pintype "bidirectional"))
    )
    (net (code "92") (name "unconnected-(IC5-SDA-Pad22)") (class "Default")
      (node (ref "IC5") (pin "22") (pinfunction "SDA_22") (pintype "bidirectional"))
    )
    (net (code "93") (name "unconnected-(U1-FAULT-Pad19)") (class "Default")
      (node (ref "U1") (pin "19") (pinfunction "FAULT_19") (pintype "bidirectional"))
    )
    (net (code "94") (name "unconnected-(U1-FW_RCVR-Pad69)") (class "Default")
      (node (ref "U1") (pin "69") (pinfunction "FW_RCVR_69") (pintype "bidirectional"))
    )
    (net (code "95") (name "unconnected-(U1-GP12_PWM0-Pad35)") (class "Default")
      (node (ref "U1") (pin "35") (pinfunction "GP12_PWM0_35") (pintype "bidirectional"))
    )
    (net (code "96") (name "unconnected-(U1-GP13_PWM1-Pad33)") (class "Default")
      (node (ref "U1") (pin "33") (pinfunction "GP13_PWM1_33") (pintype "bidirectional"))
    )
    (net (code "97") (name "unconnected-(U1-GP14-Pad48)") (class "Default")
      (node (ref "U1") (pin "48") (pinfunction "GP14_48") (pintype "bidirectional"))
    )
    (net (code "98") (name "unconnected-(U1-GP15-Pad42)") (class "Default")
      (node (ref "U1") (pin "42") (pinfunction "GP15_42") (pintype "bidirectional"))
    )
    (net (code "99") (name "unconnected-(U1-GP19_I2C_1_SCL-Pad41)") (class "Default")
      (node (ref "U1") (pin "41") (pinfunction "GP19_I2C_1_SCL_41") (pintype "bidirectional"))
    )
    (net (code "100") (name "unconnected-(U1-GP20_I2C_1_SDA-Pad43)") (class "Default")
      (node (ref "U1") (pin "43") (pinfunction "GP20_I2C_1_SDA_43") (pintype "bidirectional"))
    )
    (net (code "101") (name "unconnected-(U1-GP27_I2C_6_SCL-Pad45)") (class "Default")
      (node (ref "U1") (pin "45") (pinfunction "GP27_I2C_6_SCL_45") (pintype "bidirectional"))
    )
    (net (code "102") (name "unconnected-(U1-GP28_I2C_6_SDA-Pad47)") (class "Default")
      (node (ref "U1") (pin "47") (pinfunction "GP28_I2C_6_SDA_47") (pintype "bidirectional"))
    )
    (net (code "103") (name "unconnected-(U1-GP40_I2S_2_CLK-Pad52)") (class "Default")
      (node (ref "U1") (pin "52") (pinfunction "GP40_I2S_2_CLK_52") (pintype "bidirectional"))
    )
    (net (code "104") (name "unconnected-(U1-GP41_I2S_2_FS-Pad54)") (class "Default")
      (node (ref "U1") (pin "54") (pinfunction "GP41_I2S_2_FS_54") (pintype "bidirectional"))
    )
    (net (code "105") (name "unconnected-(U1-GP42_I2S_2_RXD-Pad50)") (class "Default")
      (node (ref "U1") (pin "50") (pinfunction "GP42_I2S_2_RXD_50") (pintype "bidirectional"))
    )
    (net (code "106") (name "unconnected-(U1-GP43_I2S_2_TXD-Pad56)") (class "Default")
      (node (ref "U1") (pin "56") (pinfunction "GP43_I2S_2_TXD_56") (pintype "bidirectional"))
    )
    (net (code "107") (name "unconnected-(U1-GP77_SD_0_CD#-Pad60)") (class "Default")
      (node (ref "U1") (pin "60") (pinfunction "GP77_SD_0_CD#_60") (pintype "bidirectional"))
    )
    (net (code "108") (name "unconnected-(U1-GP78_SD_0_CLK-Pad58)") (class "Default")
      (node (ref "U1") (pin "58") (pinfunction "GP78_SD_0_CLK_58") (pintype "bidirectional"))
    )
    (net (code "109") (name "unconnected-(U1-GP79_SD_0_CMD-Pad62)") (class "Default")
      (node (ref "U1") (pin "62") (pinfunction "GP79_SD_0_CMD_62") (pintype "bidirectional"))
    )
    (net (code "110") (name "unconnected-(U1-GP80_SD_0_DAT0-Pad66)") (class "Default")
      (node (ref "U1") (pin "66") (pinfunction "GP80_SD_0_DAT0_66") (pintype "bidirectional"))
    )
    (net (code "111") (name "unconnected-(U1-GP81_SD_0_DAT1-Pad70)") (class "Default")
      (node (ref "U1") (pin "70") (pinfunction "GP81_SD_0_DAT1_70") (pintype "bidirectional"))
    )
    (net (code "112") (name "unconnected-(U1-GP82_SD_0_DAT2-Pad64)") (class "Default")
      (node (ref "U1") (pin "64") (pinfunction "GP82_SD_0_DAT2_64") (pintype "bidirectional"))
    )
    (net (code "113") (name "unconnected-(U1-GP83_SD_0_DAT3-Pad68)") (class "Default")
      (node (ref "U1") (pin "68") (pinfunction "GP83_SD_0_DAT3_68") (pintype "bidirectional"))
    )
    (net (code "114") (name "unconnected-(U1-GP84_SD_CLK_FB-Pad44)") (class "Default")
      (node (ref "U1") (pin "44") (pinfunction "GP84_SD_CLK_FB_44") (pintype "bidirectional"))
    )
    (net (code "115") (name "unconnected-(U1-GP109_SPI_2_CLK-Pad55)") (class "Default")
      (node (ref "U1") (pin "55") (pinfunction "GP109_SPI_2_CLK_55") (pintype "bidirectional"))
    )
    (net (code "116") (name "unconnected-(U1-GP110_SPI_2_FS0-Pad53)") (class "Default")
      (node (ref "U1") (pin "53") (pinfunction "GP110_SPI_2_FS0_53") (pintype "bidirectional"))
    )
    (net (code "117") (name "unconnected-(U1-GP111_SPI_2_FS1-Pad51)") (class "Default")
      (node (ref "U1") (pin "51") (pinfunction "GP111_SPI_2_FS1_51") (pintype "bidirectional"))
    )
    (net (code "118") (name "unconnected-(U1-GP114_SPI_2_RXD-Pad59)") (class "Default")
      (node (ref "U1") (pin "59") (pinfunction "GP114_SPI_2_RXD_59") (pintype "bidirectional"))
    )
    (net (code "119") (name "unconnected-(U1-GP115_SPI_2_TXD-Pad57)") (class "Default")
      (node (ref "U1") (pin "57") (pinfunction "GP115_SPI_2_TXD_57") (pintype "bidirectional"))
    )
    (net (code "120") (name "unconnected-(U1-GP128_UART_1_CTS-Pad65)") (class "Default")
      (node (ref "U1") (pin "65") (pinfunction "GP128_UART_1_CTS_65") (pintype "bidirectional"))
    )
    (net (code "121") (name "unconnected-(U1-GP129_UART_1_RTS-Pad63)") (class "Default")
      (node (ref "U1") (pin "63") (pinfunction "GP129_UART_1_RTS_63") (pintype "bidirectional"))
    )
    (net (code "122") (name "unconnected-(U1-GP165-Pad25)") (class "Default")
      (node (ref "U1") (pin "25") (pinfunction "GP165_25") (pintype "bidirectional"))
    )
    (net (code "123") (name "unconnected-(U1-GP182_PWM2-Pad37)") (class "Default")
      (node (ref "U1") (pin "37") (pinfunction "GP182_PWM2_37") (pintype "bidirectional"))
    )
    (net (code "124") (name "unconnected-(U1-GP183_PWM3-Pad39)") (class "Default")
      (node (ref "U1") (pin "39") (pinfunction "GP183_PWM3_39") (pintype "bidirectional"))
    )
    (net (code "125") (name "unconnected-(U1-MSIC_SLP_CLK-Pad7)") (class "Default")
      (node (ref "U1") (pin "7") (pinfunction "MSIC_SLP_CLK_7") (pintype "bidirectional"))
    )
    (net (code "126") (name "unconnected-(U1-OSC_CLK_OUT_0-Pad67)") (class "Default")
      (node (ref "U1") (pin "67") (pinfunction "OSC_CLK_OUT_0_67") (pintype "bidirectional"))
    )
    (net (code "127") (name "unconnected-(U1-PSW-Pad21)") (class "Default")
      (node (ref "U1") (pin "21") (pinfunction "PSW_21") (pintype "bidirectional"))
    )
    (net (code "128") (name "unconnected-(U1-RCVR_MODE-Pad31)") (class "Default")
      (node (ref "U1") (pin "31") (pinfunction "RCVR_MODE_31") (pintype "bidirectional"))
    )
    (net (code "129") (name "unconnected-(U1-USB_VBUS-Pad20)") (class "Default")
      (node (ref "U1") (pin "20") (pinfunction "USB_VBUS_20") (pintype "bidirectional"))
    )
    (net (code "130") (name "unconnected-(U1-V_VAT_BKUP-Pad23)") (class "Default")
      (node (ref "U1") (pin "23") (pinfunction "V_VAT_BKUP_23") (pintype "bidirectional"))
    )
  )
)
